# Pixel-1.net
KiCad netlist of a schematic drawn in EAGLE
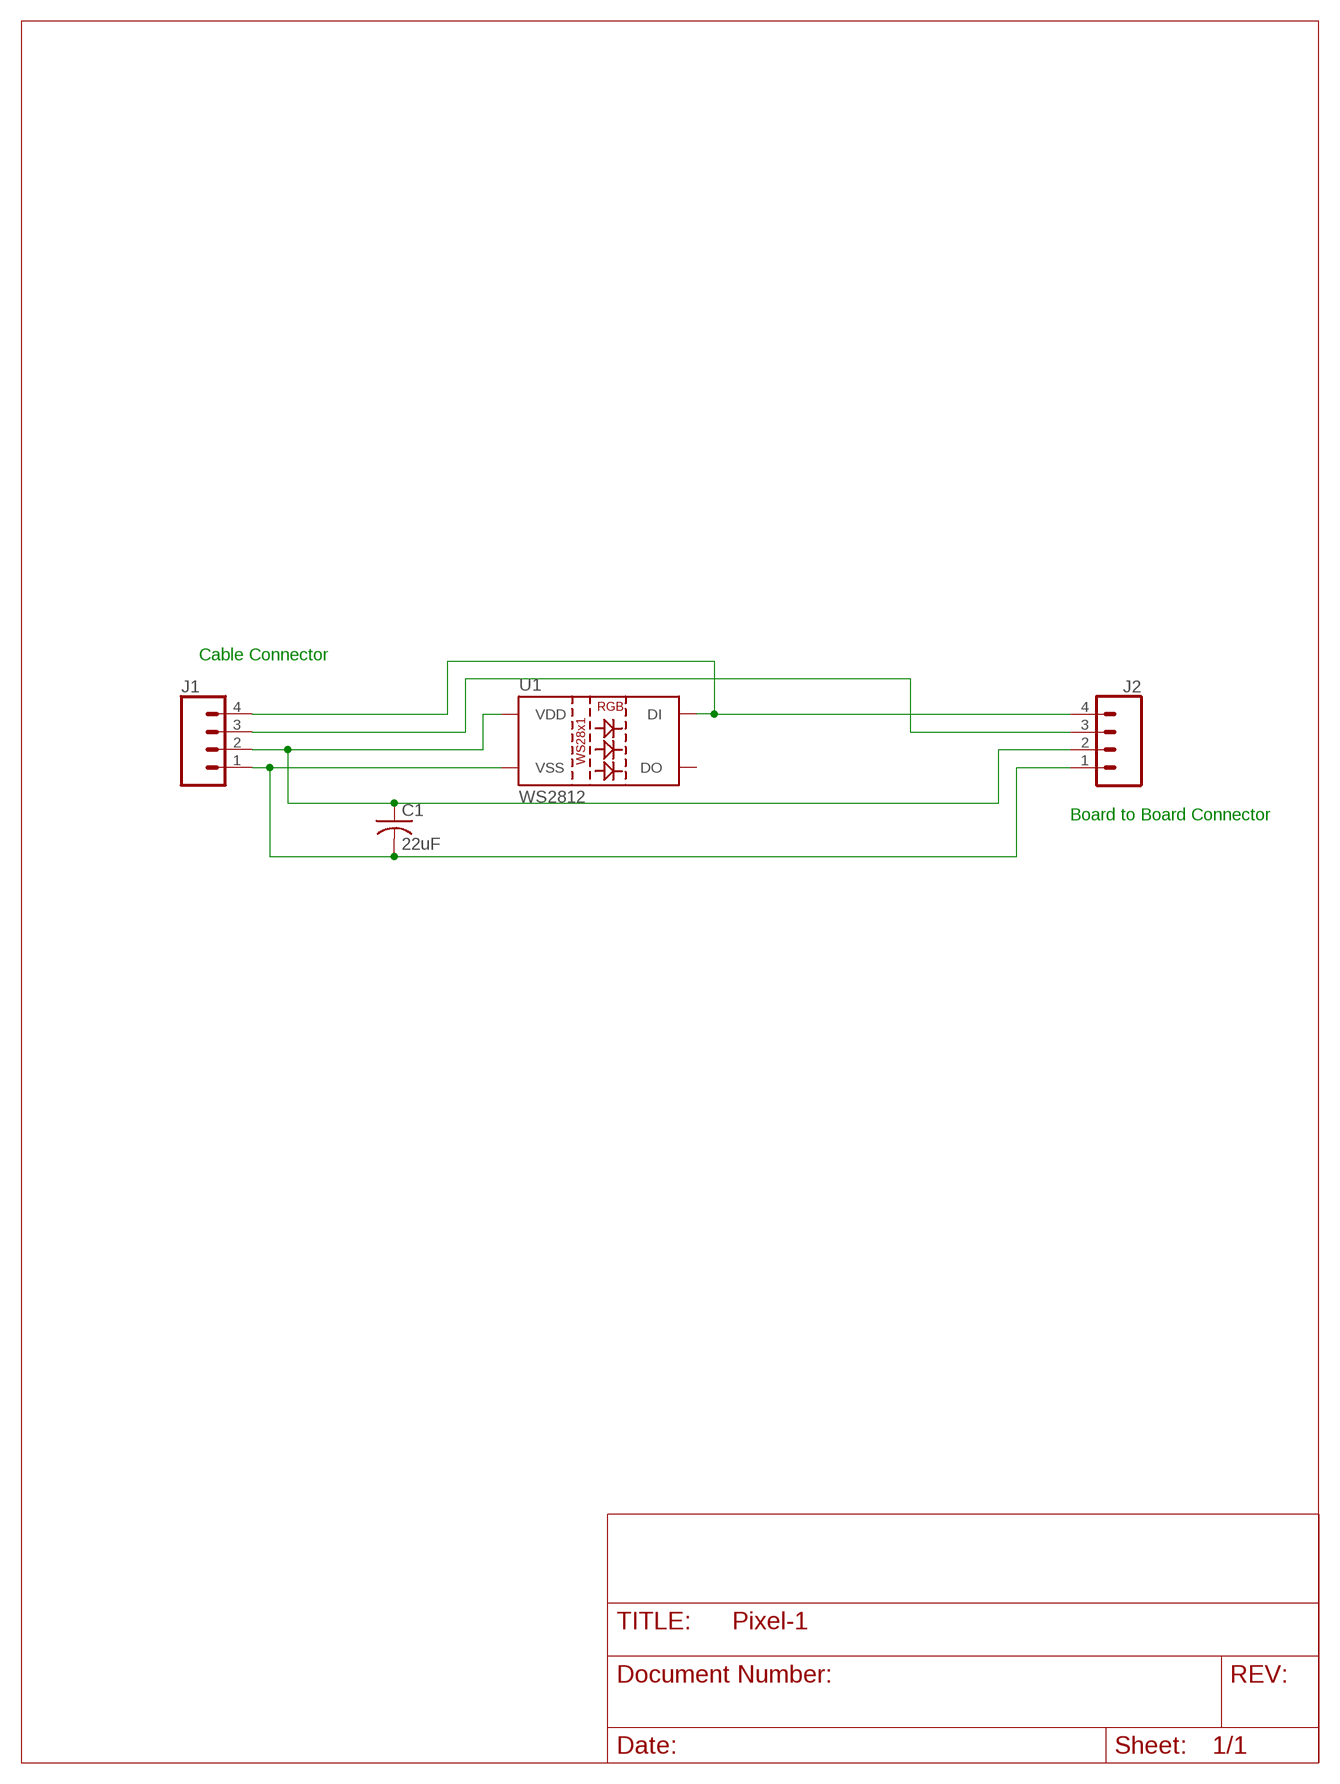
[diagram p0: schematic, sheet 1]

(export (version "E")
  (design (tool "Eeschema 10.0.6"))
  (components
    (comp (ref "C1")
      (value "22uF")
      (footprint "eagle-import:C0402")
      (libsource (lib "eagle-import") (part "C-USC0402"))
    )
    (comp (ref "J1")
      (value "CONN_04")
      (footprint "eagle-import:1X04")
      (libsource (lib "eagle-import") (part "CONN_04"))
    )
    (comp (ref "J2")
      (value "CONN_04")
      (footprint "eagle-import:1X04")
      (libsource (lib "eagle-import") (part "CONN_04"))
    )
    (comp (ref "U1")
      (value "WS2812")
      (footprint "eagle-import:LED-TRICOLOR-5050-IC")
      (libsource (lib "eagle-import") (part "WS2812{dblquote}"))
    )
  )
  (nets
    (net (code "1") (name "Net-(C1-Pad1)") (class "Default")
      (node (ref "C1") (pin "1") (pinfunction "1_1") (pintype "passive"))
      (node (ref "J1") (pin "2") (pinfunction "2_2") (pintype "passive"))
      (node (ref "J2") (pin "2") (pinfunction "2_2") (pintype "passive"))
      (node (ref "U1") (pin "3") (pinfunction "VDD_3") (pintype "bidirectional"))
      (node (ref "U1") (pin "5") (pinfunction "VDD_5") (pintype "bidirectional"))
    )
    (net (code "2") (name "Net-(J1-Pad3)") (class "Default")
      (node (ref "J1") (pin "3") (pinfunction "3_3") (pintype "passive"))
      (node (ref "J2") (pin "3") (pinfunction "3_3") (pintype "passive"))
    )
    (net (code "3") (name "Net-(U1-DI)") (class "Default")
      (node (ref "J1") (pin "4") (pinfunction "4_4") (pintype "passive"))
      (node (ref "J2") (pin "4") (pinfunction "4_4") (pintype "passive"))
      (node (ref "U1") (pin "2") (pinfunction "DI_2") (pintype "bidirectional"))
    )
    (net (code "4") (name "Net-(U1-VSS)") (class "Default")
      (node (ref "C1") (pin "2") (pinfunction "2_2") (pintype "passive"))
      (node (ref "J1") (pin "1") (pinfunction "1_1") (pintype "passive"))
      (node (ref "J2") (pin "1") (pinfunction "1_1") (pintype "passive"))
      (node (ref "U1") (pin "6") (pinfunction "VSS_6") (pintype "bidirectional"))
    )
    (net (code "5") (name "unconnected-(U1-DO-Pad1)") (class "Default")
      (node (ref "U1") (pin "1") (pinfunction "DO_1") (pintype "bidirectional"))
    )
  )
)
